# Power_Supply.net
KiCad netlist of a schematic drawn in Altium Designer
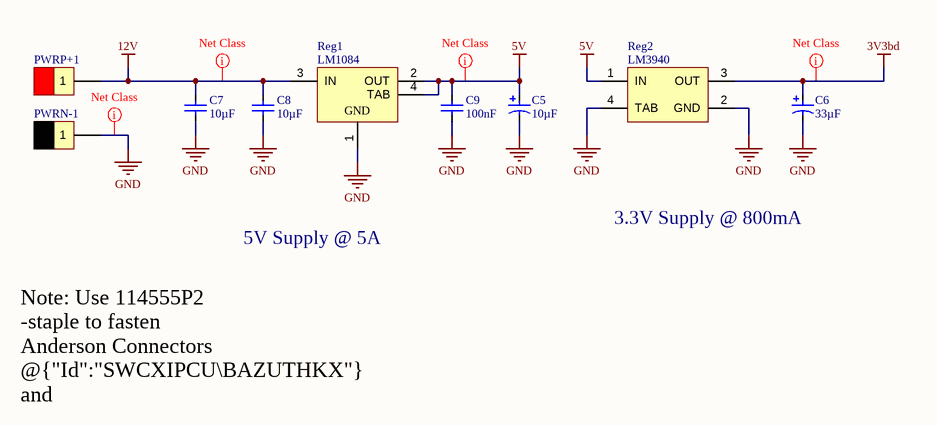
[diagram p0:  Power Supply.SchDoc]

(export (version "E")
  (design (tool "Eeschema 10.0.6"))
  (components
    (comp (ref "C5")
      (value "10µF")
      (footprint "AVX-TPSB106K020R1000_L")
      (fields
        (field (name "MANUFACTURER") "Kyocera AVX")
        (field (name "MANUFACTURER PART NUMBER") "TPSB106K020R1000")
        (field (name "Comment") "CAP Polar 10uF")
      )
      (libsource (lib "MHH -  Altium Advanced Course A365 01") (part "CMP-00072-1"))
    )
    (comp (ref "C6")
      (value "33µF")
      (footprint "FP-TAJY-MFG")
      (fields
        (field (name "MANUFACTURER") "Kyocera AVX")
        (field (name "MANUFACTURER PART NUMBER") "TAJY336K020RNJ")
        (field (name "Comment") "CAP Polar 33uF")
      )
      (libsource (lib "MHH -  Altium Advanced Course A365 01") (part "CMP-00072-1"))
    )
    (comp (ref "C7")
      (value "10µF")
      (footprint "CAPC2013X135X45ML10T25")
      (fields
        (field (name "TOLERANCE") "10%")
        (field (name "MANUFACTURER") "Murata")
        (field (name "MANUFACTURER PART NUMBER") "GRM21BR61E106KA73L")
      )
      (libsource (lib "MHH -  Altium Advanced Course A365 01") (part "CMP-00043-1"))
    )
    (comp (ref "C8")
      (value "10µF")
      (footprint "CAPC2013X135X45ML10T25")
      (fields
        (field (name "TOLERANCE") "10%")
        (field (name "MANUFACTURER") "Murata")
        (field (name "MANUFACTURER PART NUMBER") "GRM21BR61E106KA73L")
      )
      (libsource (lib "MHH -  Altium Advanced Course A365 01") (part "CMP-00043-1"))
    )
    (comp (ref "C9")
      (value "100nF")
      (footprint "0603C_L")
      (fields
        (field (name "MANUFACTURER") "Yageo")
        (field (name "MANUFACTURER PART NUMBER") "CC0603ZRY5V9BB104")
        (field (name "Comment") "CAP 100nF")
      )
      (libsource (lib "MHH -  Altium Advanced Course A365 01") (part "CMP-00119-2"))
    )
    (comp (ref "PWRN-1")
      (value "Anderson Black 1Pin")
      (footprint "Anderson_BLK_RHT_BOT")
      (description "Anderson-1Pin BLK_PCB_RHT")
      (fields
        (field (name "MANUFACTURER") "Anderson Power")
        (field (name "MANUFACTURER PART NUMBER") "1327G6")
      )
      (libsource (lib "MHH -  Altium Advanced Course A365 01") (part "Anderson Black 1Pin"))
    )
    (comp (ref "PWRP+1")
      (value "Anderson RED 1Pin")
      (footprint "Anderson_RED_RHT_BOT")
      (description "Anderson-1Pin RED_PCB_RHT")
      (fields
        (field (name "MANUFACTURER") "Anderson Power")
        (field (name "MANUFACTURER PART NUMBER") "1377G2")
      )
      (libsource (lib "MHH -  Altium Advanced Course A365 01") (part "Anderson RED 1Pin"))
    )
    (comp (ref "Reg1")
      (value "LM1084")
      (footprint "KTT0003B_L")
      (description "5A Low Dropout Positive Regulators, 3-pin TO-263, Pb-Free")
      (fields
        (field (name "MANUFACTURER") "TI National Semiconductor")
        (field (name "PARTNUMBER") "LM1084IS-5.0/NOPB")
        (field (name "SOURCE") "WCT.SchLib")
        (field (name "AVAILABLE PREVIEW IMAGES") "2D")
      )
      (libsource (lib "MHH -  Altium Advanced Course A365 01") (part "LM1084"))
    )
    (comp (ref "Reg2")
      (value "LM3940")
      (footprint "SOT223")
      (description "1A Low Dropout Regulator for 5V to 3.3V Conversion, 4-pin SOT-223, Pb-Free")
      (fields
        (field (name "MANUFACTURER") "Texas Instruments")
        (field (name "MANUFACTURER PART NUMBER") "LM3940IMP-3.3/NOPB")
        (field (name "SOURCE") "WCT.SchLib")
      )
      (libsource (lib "MHH -  Altium Advanced Course A365 01") (part "LM3940"))
    )
  )
  (nets
    (net (code "1") (name "3V3bd") (class "Default")
      (node (ref "C6") (pin "2") (pinfunction "2_2") (pintype "passive"))
      (node (ref "Reg2") (pin "3") (pinfunction "OUT_3") (pintype "power_in"))
    )
    (net (code "2") (name "5V") (class "Default")
      (node (ref "C5") (pin "2") (pinfunction "2_2") (pintype "passive"))
      (node (ref "C9") (pin "2") (pinfunction "2_2") (pintype "passive"))
      (node (ref "Reg1") (pin "2") (pinfunction "OUT_2") (pintype "power_in"))
      (node (ref "Reg1") (pin "4") (pinfunction "TAB_4") (pintype "power_in"))
      (node (ref "Reg2") (pin "1") (pinfunction "IN_1") (pintype "power_in"))
    )
    (net (code "3") (name "12V") (class "Default")
      (node (ref "C7") (pin "2") (pinfunction "2_2") (pintype "passive"))
      (node (ref "C8") (pin "2") (pinfunction "2_2") (pintype "passive"))
      (node (ref "PWRP+1") (pin "1") (pinfunction "1_1") (pintype "passive"))
      (node (ref "Reg1") (pin "3") (pinfunction "IN_3") (pintype "power_in"))
    )
    (net (code "4") (name "GND") (class "Default")
      (node (ref "C5") (pin "1") (pinfunction "1_1") (pintype "passive"))
      (node (ref "C6") (pin "1") (pinfunction "1_1") (pintype "passive"))
      (node (ref "C7") (pin "1") (pinfunction "1_1") (pintype "passive"))
      (node (ref "C8") (pin "1") (pinfunction "1_1") (pintype "passive"))
      (node (ref "C9") (pin "1") (pinfunction "1_1") (pintype "passive"))
      (node (ref "PWRN-1") (pin "1") (pinfunction "1_1") (pintype "passive"))
      (node (ref "Reg1") (pin "1") (pinfunction "GND_1") (pintype "power_in"))
      (node (ref "Reg2") (pin "2") (pinfunction "GND_2") (pintype "power_in"))
      (node (ref "Reg2") (pin "4") (pinfunction "TAB_4") (pintype "power_in"))
    )
  )
)
